# right_sub.net
KiCad netlist of a schematic drawn in Altium Designer
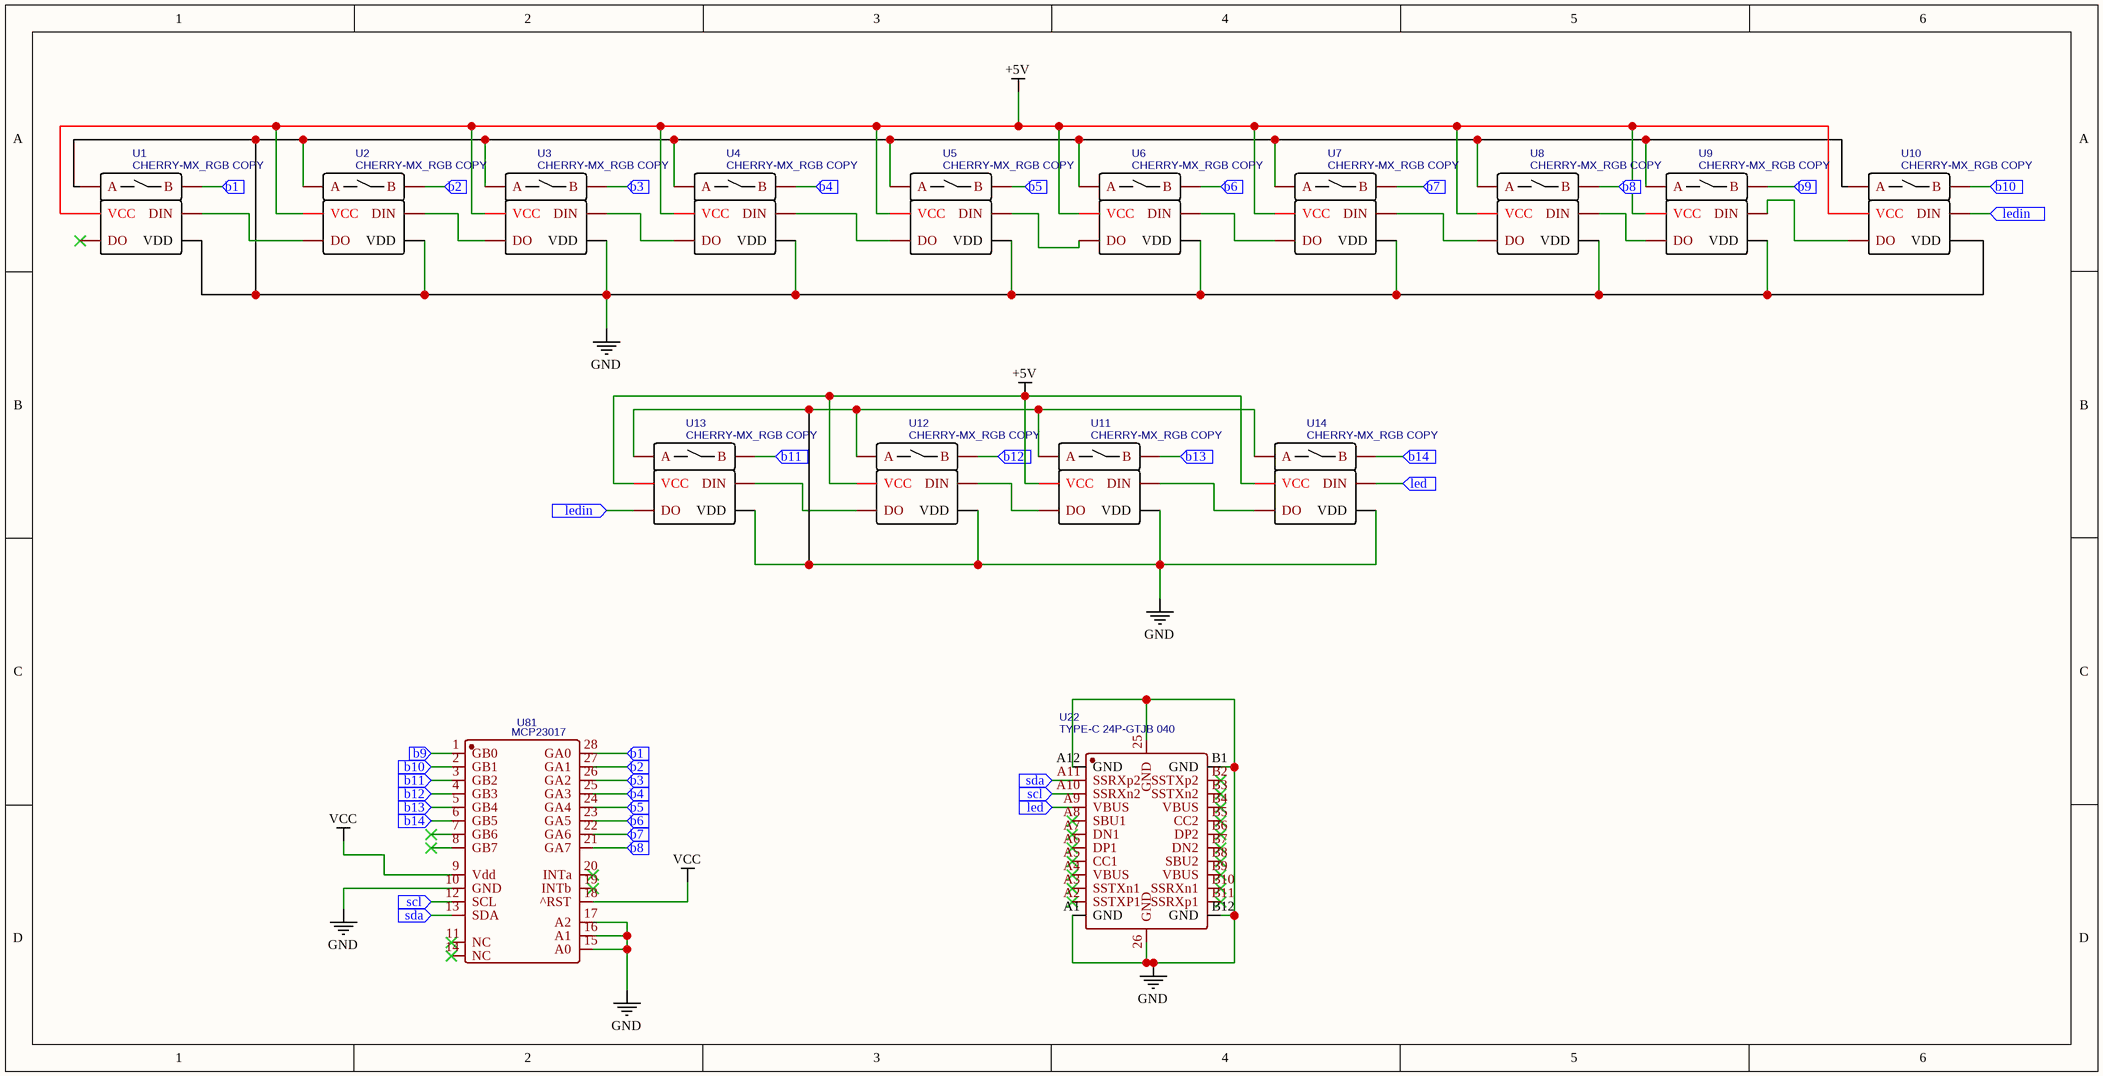
[diagram p0: right sub.schdoc]

(export (version "E")
  (design (tool "Eeschema 10.0.6"))
  (components
    (comp (ref "U1")
      (value "CHERRY-MX_RGB COPY")
      (fields (field (name "CONTRIBUTOR") "unrealin01"))
      (libsource (lib "altium-import") (part "root_0_CHERRY-MX_RGB COPY_"))
    )
    (comp (ref "U2")
      (value "CHERRY-MX_RGB COPY")
      (fields (field (name "CONTRIBUTOR") "unrealin01"))
      (libsource (lib "altium-import") (part "root_0_CHERRY-MX_RGB COPY_"))
    )
    (comp (ref "U3")
      (value "CHERRY-MX_RGB COPY")
      (fields (field (name "CONTRIBUTOR") "unrealin01"))
      (libsource (lib "altium-import") (part "root_0_CHERRY-MX_RGB COPY_"))
    )
    (comp (ref "U4")
      (value "CHERRY-MX_RGB COPY")
      (fields (field (name "CONTRIBUTOR") "unrealin01"))
      (libsource (lib "altium-import") (part "root_0_CHERRY-MX_RGB COPY_"))
    )
    (comp (ref "U5")
      (value "CHERRY-MX_RGB COPY")
      (fields (field (name "CONTRIBUTOR") "unrealin01"))
      (libsource (lib "altium-import") (part "root_0_CHERRY-MX_RGB COPY_"))
    )
    (comp (ref "U6")
      (value "CHERRY-MX_RGB COPY")
      (fields (field (name "CONTRIBUTOR") "unrealin01"))
      (libsource (lib "altium-import") (part "root_0_CHERRY-MX_RGB COPY_"))
    )
    (comp (ref "U7")
      (value "CHERRY-MX_RGB COPY")
      (fields (field (name "CONTRIBUTOR") "unrealin01"))
      (libsource (lib "altium-import") (part "root_0_CHERRY-MX_RGB COPY_"))
    )
    (comp (ref "U8")
      (value "CHERRY-MX_RGB COPY")
      (fields (field (name "CONTRIBUTOR") "unrealin01"))
      (libsource (lib "altium-import") (part "root_0_CHERRY-MX_RGB COPY_"))
    )
    (comp (ref "U9")
      (value "CHERRY-MX_RGB COPY")
      (fields (field (name "CONTRIBUTOR") "unrealin01"))
      (libsource (lib "altium-import") (part "root_0_CHERRY-MX_RGB COPY_"))
    )
    (comp (ref "U10")
      (value "CHERRY-MX_RGB COPY")
      (fields (field (name "CONTRIBUTOR") "unrealin01"))
      (libsource (lib "altium-import") (part "root_0_CHERRY-MX_RGB COPY_"))
    )
    (comp (ref "U11")
      (value "CHERRY-MX_RGB COPY")
      (fields (field (name "CONTRIBUTOR") "unrealin01"))
      (libsource (lib "altium-import") (part "root_0_CHERRY-MX_RGB COPY_"))
    )
    (comp (ref "U12")
      (value "CHERRY-MX_RGB COPY")
      (fields (field (name "CONTRIBUTOR") "unrealin01"))
      (libsource (lib "altium-import") (part "root_0_CHERRY-MX_RGB COPY_"))
    )
    (comp (ref "U13")
      (value "CHERRY-MX_RGB COPY")
      (fields (field (name "CONTRIBUTOR") "unrealin01"))
      (libsource (lib "altium-import") (part "root_0_CHERRY-MX_RGB COPY_"))
    )
    (comp (ref "U14")
      (value "CHERRY-MX_RGB COPY")
      (fields (field (name "CONTRIBUTOR") "unrealin01"))
      (libsource (lib "altium-import") (part "root_0_CHERRY-MX_RGB COPY_"))
    )
    (comp (ref "U22")
      (value "TYPE-C 24P-GTJB 040")
      (fields (field (name "MANUFACTURER") "SHOU HAN(首韩)") (field (name "CONTRIBUTOR") "lcsc"))
      (libsource (lib "altium-import") (part "root_0_TYPE-C 24P-GTJB 040_"))
    )
    (comp (ref "U81")
      (value "MCP23017")
      (fields (field (name "CONTRIBUTOR") "tsvstar"))
      (libsource (lib "altium-import") (part "root_0_MCP23017_"))
    )
  )
  (nets
    (net (code "1") (name "+5V") (class "Default")
      (node (ref "U1") (pin "3") (pinfunction "VCC_3") (pintype "passive"))
      (node (ref "U10") (pin "3") (pinfunction "VCC_3") (pintype "passive"))
      (node (ref "U11") (pin "3") (pinfunction "VCC_3") (pintype "passive"))
      (node (ref "U12") (pin "3") (pinfunction "VCC_3") (pintype "passive"))
      (node (ref "U13") (pin "3") (pinfunction "VCC_3") (pintype "passive"))
      (node (ref "U14") (pin "3") (pinfunction "VCC_3") (pintype "passive"))
      (node (ref "U2") (pin "3") (pinfunction "VCC_3") (pintype "passive"))
      (node (ref "U3") (pin "3") (pinfunction "VCC_3") (pintype "passive"))
      (node (ref "U4") (pin "3") (pinfunction "VCC_3") (pintype "passive"))
      (node (ref "U5") (pin "3") (pinfunction "VCC_3") (pintype "passive"))
      (node (ref "U6") (pin "3") (pinfunction "VCC_3") (pintype "passive"))
      (node (ref "U7") (pin "3") (pinfunction "VCC_3") (pintype "passive"))
      (node (ref "U8") (pin "3") (pinfunction "VCC_3") (pintype "passive"))
      (node (ref "U9") (pin "3") (pinfunction "VCC_3") (pintype "passive"))
    )
    (net (code "2") (name "/b1") (class "Default")
      (node (ref "U1") (pin "2") (pinfunction "B_2") (pintype "passive"))
      (node (ref "U81") (pin "28") (pinfunction "GA0_28") (pintype "passive"))
    )
    (net (code "3") (name "/b2") (class "Default")
      (node (ref "U2") (pin "2") (pinfunction "B_2") (pintype "passive"))
      (node (ref "U81") (pin "27") (pinfunction "GA1_27") (pintype "passive"))
    )
    (net (code "4") (name "/b3") (class "Default")
      (node (ref "U3") (pin "2") (pinfunction "B_2") (pintype "passive"))
      (node (ref "U81") (pin "26") (pinfunction "GA2_26") (pintype "passive"))
    )
    (net (code "5") (name "/b4") (class "Default")
      (node (ref "U4") (pin "2") (pinfunction "B_2") (pintype "passive"))
      (node (ref "U81") (pin "25") (pinfunction "GA3_25") (pintype "passive"))
    )
    (net (code "6") (name "/b5") (class "Default")
      (node (ref "U5") (pin "2") (pinfunction "B_2") (pintype "passive"))
      (node (ref "U81") (pin "24") (pinfunction "GA4_24") (pintype "passive"))
    )
    (net (code "7") (name "/b6") (class "Default")
      (node (ref "U6") (pin "2") (pinfunction "B_2") (pintype "passive"))
      (node (ref "U81") (pin "23") (pinfunction "GA5_23") (pintype "passive"))
    )
    (net (code "8") (name "/b7") (class "Default")
      (node (ref "U7") (pin "2") (pinfunction "B_2") (pintype "passive"))
      (node (ref "U81") (pin "22") (pinfunction "GA6_22") (pintype "passive"))
    )
    (net (code "9") (name "/b8") (class "Default")
      (node (ref "U8") (pin "2") (pinfunction "B_2") (pintype "passive"))
      (node (ref "U81") (pin "21") (pinfunction "GA7_21") (pintype "passive"))
    )
    (net (code "10") (name "/b9") (class "Default")
      (node (ref "U81") (pin "1") (pinfunction "GB0_1") (pintype "passive"))
      (node (ref "U9") (pin "2") (pinfunction "B_2") (pintype "passive"))
    )
    (net (code "11") (name "/b10") (class "Default")
      (node (ref "U10") (pin "2") (pinfunction "B_2") (pintype "passive"))
      (node (ref "U81") (pin "2") (pinfunction "GB1_2") (pintype "passive"))
    )
    (net (code "12") (name "/b11") (class "Default")
      (node (ref "U13") (pin "2") (pinfunction "B_2") (pintype "passive"))
      (node (ref "U81") (pin "3") (pinfunction "GB2_3") (pintype "passive"))
    )
    (net (code "13") (name "/b12") (class "Default")
      (node (ref "U12") (pin "2") (pinfunction "B_2") (pintype "passive"))
      (node (ref "U81") (pin "4") (pinfunction "GB3_4") (pintype "passive"))
    )
    (net (code "14") (name "/b13") (class "Default")
      (node (ref "U11") (pin "2") (pinfunction "B_2") (pintype "passive"))
      (node (ref "U81") (pin "5") (pinfunction "GB4_5") (pintype "passive"))
    )
    (net (code "15") (name "/b14") (class "Default")
      (node (ref "U14") (pin "2") (pinfunction "B_2") (pintype "passive"))
      (node (ref "U81") (pin "6") (pinfunction "GB5_6") (pintype "passive"))
    )
    (net (code "16") (name "/led") (class "Default")
      (node (ref "U14") (pin "6") (pinfunction "DIN_6") (pintype "passive"))
      (node (ref "U22") (pin "A9") (pinfunction "VBUS_A9") (pintype "passive"))
    )
    (net (code "17") (name "/ledin") (class "Default")
      (node (ref "U10") (pin "6") (pinfunction "DIN_6") (pintype "passive"))
      (node (ref "U13") (pin "4") (pinfunction "DO_4") (pintype "passive"))
    )
    (net (code "18") (name "/scl") (class "Default")
      (node (ref "U22") (pin "A10") (pinfunction "SSRXn2_A10") (pintype "passive"))
      (node (ref "U81") (pin "12") (pinfunction "SCL_12") (pintype "passive"))
    )
    (net (code "19") (name "/sda") (class "Default")
      (node (ref "U22") (pin "A11") (pinfunction "SSRXp2_A11") (pintype "passive"))
      (node (ref "U81") (pin "13") (pinfunction "SDA_13") (pintype "passive"))
    )
    (net (code "20") (name "GND") (class "Default")
      (node (ref "U1") (pin "1") (pinfunction "A_1") (pintype "passive"))
      (node (ref "U1") (pin "5") (pinfunction "VDD_5") (pintype "passive"))
      (node (ref "U10") (pin "1") (pinfunction "A_1") (pintype "passive"))
      (node (ref "U10") (pin "5") (pinfunction "VDD_5") (pintype "passive"))
      (node (ref "U11") (pin "1") (pinfunction "A_1") (pintype "passive"))
      (node (ref "U11") (pin "5") (pinfunction "VDD_5") (pintype "passive"))
      (node (ref "U12") (pin "1") (pinfunction "A_1") (pintype "passive"))
      (node (ref "U12") (pin "5") (pinfunction "VDD_5") (pintype "passive"))
      (node (ref "U13") (pin "1") (pinfunction "A_1") (pintype "passive"))
      (node (ref "U13") (pin "5") (pinfunction "VDD_5") (pintype "passive"))
      (node (ref "U14") (pin "1") (pinfunction "A_1") (pintype "passive"))
      (node (ref "U14") (pin "5") (pinfunction "VDD_5") (pintype "passive"))
      (node (ref "U2") (pin "1") (pinfunction "A_1") (pintype "passive"))
      (node (ref "U2") (pin "5") (pinfunction "VDD_5") (pintype "passive"))
      (node (ref "U22") (pin "25") (pinfunction "GND_25") (pintype "passive"))
      (node (ref "U22") (pin "26") (pinfunction "GND_26") (pintype "passive"))
      (node (ref "U22") (pin "A1") (pinfunction "GND_A1") (pintype "passive"))
      (node (ref "U22") (pin "A12") (pinfunction "GND_A12") (pintype "passive"))
      (node (ref "U22") (pin "B1") (pinfunction "GND_B1") (pintype "passive"))
      (node (ref "U22") (pin "B12") (pinfunction "GND_B12") (pintype "passive"))
      (node (ref "U3") (pin "1") (pinfunction "A_1") (pintype "passive"))
      (node (ref "U3") (pin "5") (pinfunction "VDD_5") (pintype "passive"))
      (node (ref "U4") (pin "1") (pinfunction "A_1") (pintype "passive"))
      (node (ref "U4") (pin "5") (pinfunction "VDD_5") (pintype "passive"))
      (node (ref "U5") (pin "1") (pinfunction "A_1") (pintype "passive"))
      (node (ref "U5") (pin "5") (pinfunction "VDD_5") (pintype "passive"))
      (node (ref "U6") (pin "1") (pinfunction "A_1") (pintype "passive"))
      (node (ref "U6") (pin "5") (pinfunction "VDD_5") (pintype "passive"))
      (node (ref "U7") (pin "1") (pinfunction "A_1") (pintype "passive"))
      (node (ref "U7") (pin "5") (pinfunction "VDD_5") (pintype "passive"))
      (node (ref "U8") (pin "1") (pinfunction "A_1") (pintype "passive"))
      (node (ref "U8") (pin "5") (pinfunction "VDD_5") (pintype "passive"))
      (node (ref "U81") (pin "10") (pinfunction "GND_10") (pintype "passive"))
      (node (ref "U81") (pin "15") (pinfunction "A0_15") (pintype "passive"))
      (node (ref "U81") (pin "16") (pinfunction "A1_16") (pintype "passive"))
      (node (ref "U81") (pin "17") (pinfunction "A2_17") (pintype "passive"))
      (node (ref "U9") (pin "1") (pinfunction "A_1") (pintype "passive"))
      (node (ref "U9") (pin "5") (pinfunction "VDD_5") (pintype "passive"))
    )
    (net (code "21") (name "Net-(U1-DIN)") (class "Default")
      (node (ref "U1") (pin "6") (pinfunction "DIN_6") (pintype "passive"))
      (node (ref "U2") (pin "4") (pinfunction "DO_4") (pintype "passive"))
    )
    (net (code "22") (name "Net-(U2-DIN)") (class "Default")
      (node (ref "U2") (pin "6") (pinfunction "DIN_6") (pintype "passive"))
      (node (ref "U3") (pin "4") (pinfunction "DO_4") (pintype "passive"))
    )
    (net (code "23") (name "Net-(U3-DIN)") (class "Default")
      (node (ref "U3") (pin "6") (pinfunction "DIN_6") (pintype "passive"))
      (node (ref "U4") (pin "4") (pinfunction "DO_4") (pintype "passive"))
    )
    (net (code "24") (name "Net-(U4-DIN)") (class "Default")
      (node (ref "U4") (pin "6") (pinfunction "DIN_6") (pintype "passive"))
      (node (ref "U5") (pin "4") (pinfunction "DO_4") (pintype "passive"))
    )
    (net (code "25") (name "Net-(U5-DIN)") (class "Default")
      (node (ref "U5") (pin "6") (pinfunction "DIN_6") (pintype "passive"))
      (node (ref "U6") (pin "4") (pinfunction "DO_4") (pintype "passive"))
    )
    (net (code "26") (name "Net-(U6-DIN)") (class "Default")
      (node (ref "U6") (pin "6") (pinfunction "DIN_6") (pintype "passive"))
      (node (ref "U7") (pin "4") (pinfunction "DO_4") (pintype "passive"))
    )
    (net (code "27") (name "Net-(U7-DIN)") (class "Default")
      (node (ref "U7") (pin "6") (pinfunction "DIN_6") (pintype "passive"))
      (node (ref "U8") (pin "4") (pinfunction "DO_4") (pintype "passive"))
    )
    (net (code "28") (name "Net-(U8-DIN)") (class "Default")
      (node (ref "U8") (pin "6") (pinfunction "DIN_6") (pintype "passive"))
      (node (ref "U9") (pin "4") (pinfunction "DO_4") (pintype "passive"))
    )
    (net (code "29") (name "Net-(U10-DO)") (class "Default")
      (node (ref "U10") (pin "4") (pinfunction "DO_4") (pintype "passive"))
      (node (ref "U9") (pin "6") (pinfunction "DIN_6") (pintype "passive"))
    )
    (net (code "30") (name "Net-(U11-DIN)") (class "Default")
      (node (ref "U11") (pin "6") (pinfunction "DIN_6") (pintype "passive"))
      (node (ref "U14") (pin "4") (pinfunction "DO_4") (pintype "passive"))
    )
    (net (code "31") (name "Net-(U11-DO)") (class "Default")
      (node (ref "U11") (pin "4") (pinfunction "DO_4") (pintype "passive"))
      (node (ref "U12") (pin "6") (pinfunction "DIN_6") (pintype "passive"))
    )
    (net (code "32") (name "Net-(U12-DO)") (class "Default")
      (node (ref "U12") (pin "4") (pinfunction "DO_4") (pintype "passive"))
      (node (ref "U13") (pin "6") (pinfunction "DIN_6") (pintype "passive"))
    )
    (net (code "33") (name "VCC") (class "Default")
      (node (ref "U81") (pin "18") (pinfunction "^RST_18") (pintype "passive"))
      (node (ref "U81") (pin "9") (pinfunction "Vdd_9") (pintype "passive"))
    )
    (net (code "34") (name "unconnected-(U1-DO-Pad4)") (class "Default")
      (node (ref "U1") (pin "4") (pinfunction "DO_4") (pintype "passive+no_connect"))
    )
    (net (code "35") (name "unconnected-(U22-CC1-PadA5)") (class "Default")
      (node (ref "U22") (pin "A5") (pinfunction "CC1_A5") (pintype "passive+no_connect"))
    )
    (net (code "36") (name "unconnected-(U22-CC2-PadB5)") (class "Default")
      (node (ref "U22") (pin "B5") (pinfunction "CC2_B5") (pintype "passive+no_connect"))
    )
    (net (code "37") (name "unconnected-(U22-DN1-PadA7)") (class "Default")
      (node (ref "U22") (pin "A7") (pinfunction "DN1_A7") (pintype "passive+no_connect"))
    )
    (net (code "38") (name "unconnected-(U22-DN2-PadB7)") (class "Default")
      (node (ref "U22") (pin "B7") (pinfunction "DN2_B7") (pintype "passive+no_connect"))
    )
    (net (code "39") (name "unconnected-(U22-DP1-PadA6)") (class "Default")
      (node (ref "U22") (pin "A6") (pinfunction "DP1_A6") (pintype "passive+no_connect"))
    )
    (net (code "40") (name "unconnected-(U22-DP2-PadB6)") (class "Default")
      (node (ref "U22") (pin "B6") (pinfunction "DP2_B6") (pintype "passive+no_connect"))
    )
    (net (code "41") (name "unconnected-(U22-SBU1-PadA8)") (class "Default")
      (node (ref "U22") (pin "A8") (pinfunction "SBU1_A8") (pintype "passive+no_connect"))
    )
    (net (code "42") (name "unconnected-(U22-SBU2-PadB8)") (class "Default")
      (node (ref "U22") (pin "B8") (pinfunction "SBU2_B8") (pintype "passive+no_connect"))
    )
    (net (code "43") (name "unconnected-(U22-SSRXn1-PadB10)") (class "Default")
      (node (ref "U22") (pin "B10") (pinfunction "SSRXn1_B10") (pintype "passive+no_connect"))
    )
    (net (code "44") (name "unconnected-(U22-SSRXp1-PadB11)") (class "Default")
      (node (ref "U22") (pin "B11") (pinfunction "SSRXp1_B11") (pintype "passive+no_connect"))
    )
    (net (code "45") (name "unconnected-(U22-SSTXP1-PadA2)") (class "Default")
      (node (ref "U22") (pin "A2") (pinfunction "SSTXP1_A2") (pintype "passive+no_connect"))
    )
    (net (code "46") (name "unconnected-(U22-SSTXn1-PadA3)") (class "Default")
      (node (ref "U22") (pin "A3") (pinfunction "SSTXn1_A3") (pintype "passive+no_connect"))
    )
    (net (code "47") (name "unconnected-(U22-SSTXn2-PadB3)") (class "Default")
      (node (ref "U22") (pin "B3") (pinfunction "SSTXn2_B3") (pintype "passive+no_connect"))
    )
    (net (code "48") (name "unconnected-(U22-SSTXp2-PadB2)") (class "Default")
      (node (ref "U22") (pin "B2") (pinfunction "SSTXp2_B2") (pintype "passive+no_connect"))
    )
    (net (code "49") (name "unconnected-(U22-VBUS-PadA4)") (class "Default")
      (node (ref "U22") (pin "A4") (pinfunction "VBUS_A4") (pintype "passive+no_connect"))
    )
    (net (code "50") (name "unconnected-(U22-VBUS-PadB4)") (class "Default")
      (node (ref "U22") (pin "B4") (pinfunction "VBUS_B4") (pintype "passive+no_connect"))
    )
    (net (code "51") (name "unconnected-(U22-VBUS-PadB9)") (class "Default")
      (node (ref "U22") (pin "B9") (pinfunction "VBUS_B9") (pintype "passive+no_connect"))
    )
    (net (code "52") (name "unconnected-(U81-GB6-Pad7)") (class "Default")
      (node (ref "U81") (pin "7") (pinfunction "GB6_7") (pintype "passive+no_connect"))
    )
    (net (code "53") (name "unconnected-(U81-GB7-Pad8)") (class "Default")
      (node (ref "U81") (pin "8") (pinfunction "GB7_8") (pintype "passive+no_connect"))
    )
    (net (code "54") (name "unconnected-(U81-INTa-Pad20)") (class "Default")
      (node (ref "U81") (pin "20") (pinfunction "INTa_20") (pintype "passive+no_connect"))
    )
    (net (code "55") (name "unconnected-(U81-INTb-Pad19)") (class "Default")
      (node (ref "U81") (pin "19") (pinfunction "INTb_19") (pintype "passive+no_connect"))
    )
    (net (code "56") (name "unconnected-(U81-NC-Pad11)") (class "Default")
      (node (ref "U81") (pin "11") (pinfunction "NC_11") (pintype "passive+no_connect"))
    )
    (net (code "57") (name "unconnected-(U81-NC-Pad14)") (class "Default")
      (node (ref "U81") (pin "14") (pinfunction "NC_14") (pintype "passive+no_connect"))
    )
  )
)
